# TEST_Capteurs_et_Antenne.net
KiCad netlist of a schematic drawn in Altium Designer
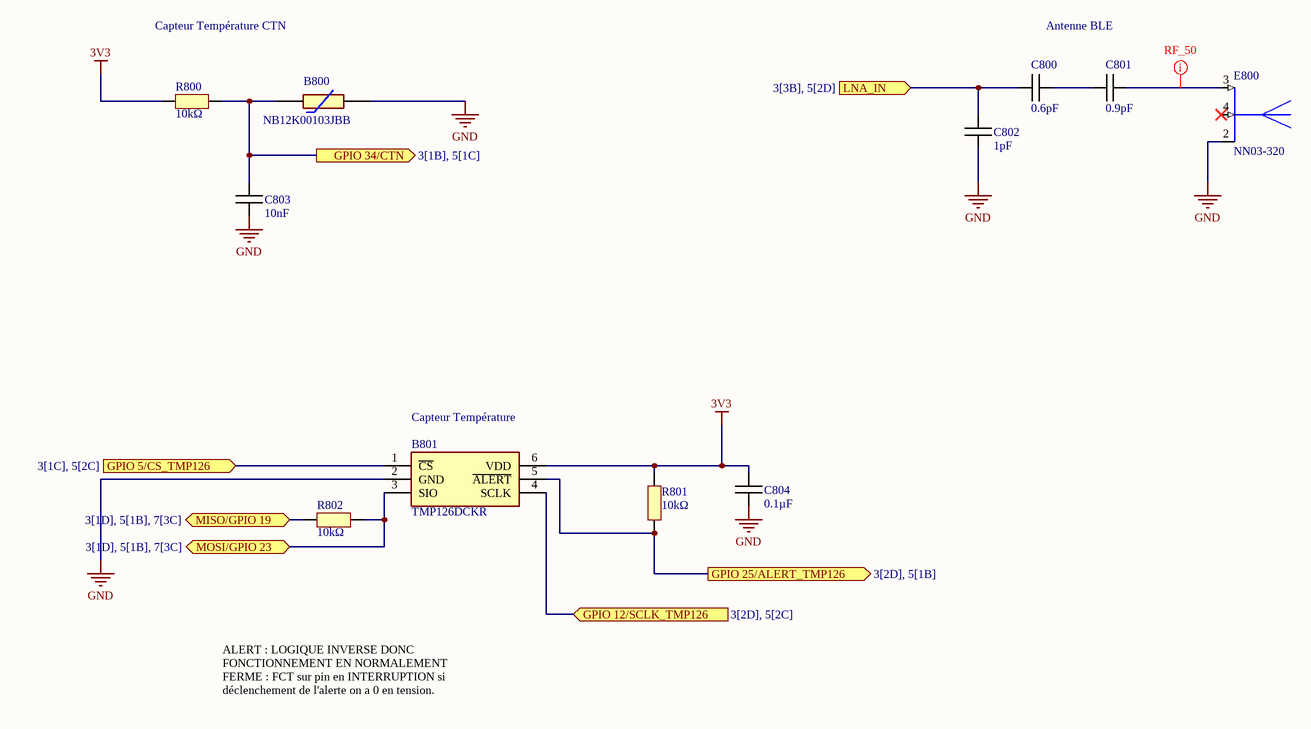
[diagram p0: TEST_Capteurs_et_Antenne.SchDoc]

(export (version "E")
  (design (tool "Eeschema 10.0.6"))
  (components
    (comp (ref "B800")
      (value "NB12K00103JBB")
      (footprint "RESC2212X50N")
      (fields (field (name "MOUSER PART NUMBER") "581-NB12K00103JBB"))
      (libsource (lib "SCHLibrary") (part "NB12K00103JBB"))
    )
    (comp (ref "B801")
      (value "TMP126DCKR")
      (footprint "SOT65P210X110-6N")
      (fields (field (name "MOUSER PART NUMBER") "595-TMP126DCKR"))
      (libsource (lib "SCHLibrary") (part "TMP126DCKR"))
    )
    (comp (ref "C800")
      (value "0.6pF")
      (footprint "CAPC1005X06N")
      (libsource (lib "SCHLibrary") (part "Capacitor"))
    )
    (comp (ref "C801")
      (value "0.9pF")
      (footprint "CAPC1005X06N")
      (libsource (lib "SCHLibrary") (part "Capacitor"))
    )
    (comp (ref "C802")
      (value "1pF")
      (footprint "CAPC1005X06N")
      (libsource (lib "SCHLibrary") (part "Capacitor"))
    )
    (comp (ref "C803")
      (value "10nF")
      (footprint "CAPC1005X06N")
      (libsource (lib "SCHLibrary") (part "Capacitor"))
    )
    (comp (ref "C804")
      (value "0.1µF")
      (footprint "CAPC1005X06N")
      (libsource (lib "SCHLibrary") (part "Capacitor"))
    )
    (comp (ref "E800")
      (value "NN03-320")
      (footprint "XCVR_NN03-320")
      (fields (field (name "MOUSER PART NUMBER") "128-NN03-320"))
      (libsource (lib "SCHLibrary") (part "NN03-320"))
    )
    (comp (ref "R800")
      (value "10kΩ")
      (footprint "RESC1005X06N")
      (libsource (lib "SCHLibrary") (part "Resistor"))
    )
    (comp (ref "R801") (value "10kΩ") (footprint "RESC1005X06N") (libsource (lib "") (part "Resistor_1")))
    (comp (ref "R802")
      (value "10kΩ")
      (footprint "RESC1005X06N")
      (libsource (lib "SCHLibrary") (part "Resistor"))
    )
  )
  (nets
    (net (code "1") (name "/GPIO 5{slash}CS_TMP126") (class "Default")
      (node (ref "B801") (pin "1") (pinfunction "~{CS}_1") (pintype "passive"))
    )
    (net (code "2") (name "/GPIO 12{slash}SCLK_TMP126") (class "Default")
      (node (ref "B801") (pin "4") (pinfunction "SCLK_4") (pintype "passive"))
    )
    (net (code "3") (name "/GPIO 25{slash}ALERT_TMP126") (class "Default")
      (node (ref "B801") (pin "5") (pinfunction "~{ALERT}_5") (pintype "passive"))
      (node (ref "R801") (pin "1") (pinfunction "1_1") (pintype "passive"))
    )
    (net (code "4") (name "/GPIO 34{slash}CTN") (class "Default")
      (node (ref "B800") (pin "1") (pinfunction "1_1") (pintype "passive"))
      (node (ref "C803") (pin "1") (pinfunction "1_1") (pintype "passive"))
      (node (ref "R800") (pin "2") (pinfunction "2_2") (pintype "passive"))
    )
    (net (code "5") (name "/LNA_IN") (class "Default")
      (node (ref "C800") (pin "2") (pinfunction "2_2") (pintype "passive"))
      (node (ref "C802") (pin "2") (pinfunction "2_2") (pintype "passive"))
    )
    (net (code "6") (name "/MISO{slash}GPIO 19") (class "Default")
      (node (ref "R802") (pin "1") (pinfunction "1_1") (pintype "passive"))
    )
    (net (code "7") (name "/MOSI{slash}GPIO 23") (class "Default")
      (node (ref "B801") (pin "3") (pinfunction "SIO_3") (pintype "passive"))
      (node (ref "R802") (pin "2") (pinfunction "2_2") (pintype "passive"))
    )
    (net (code "8") (name "3V3") (class "Default")
      (node (ref "B801") (pin "6") (pinfunction "VDD_6") (pintype "passive"))
      (node (ref "C804") (pin "1") (pinfunction "1_1") (pintype "passive"))
      (node (ref "R800") (pin "1") (pinfunction "1_1") (pintype "passive"))
      (node (ref "R801") (pin "2") (pinfunction "2_2") (pintype "passive"))
    )
    (net (code "9") (name "GND") (class "Default")
      (node (ref "B800") (pin "2") (pinfunction "2_2") (pintype "passive"))
      (node (ref "B801") (pin "2") (pinfunction "GND_2") (pintype "passive"))
      (node (ref "C802") (pin "1") (pinfunction "1_1") (pintype "passive"))
      (node (ref "C803") (pin "2") (pinfunction "2_2") (pintype "passive"))
      (node (ref "C804") (pin "2") (pinfunction "2_2") (pintype "passive"))
      (node (ref "E800") (pin "2") (pinfunction "GROUND_2") (pintype "power_in"))
    )
    (net (code "10") (name "Net-(C800-Pad1)") (class "Default")
      (node (ref "C800") (pin "1") (pinfunction "1_1") (pintype "passive"))
      (node (ref "C801") (pin "1") (pinfunction "1_1") (pintype "passive"))
    )
    (net (code "11") (name "Net-(E800-FEED_BLUETOOTH)") (class "Default")
      (node (ref "C801") (pin "2") (pinfunction "2_2") (pintype "passive"))
      (node (ref "E800") (pin "3") (pinfunction "FEED_BLUETOOTH_3") (pintype "input"))
    )
    (net (code "12") (name "unconnected-(E800-FEED_GNSS-Pad4)") (class "Default")
      (node (ref "E800") (pin "4") (pinfunction "FEED_GNSS_4") (pintype "input+no_connect"))
    )
  )
)
